# MCP4725_Breakout.net
KiCad netlist of a schematic drawn in EAGLE
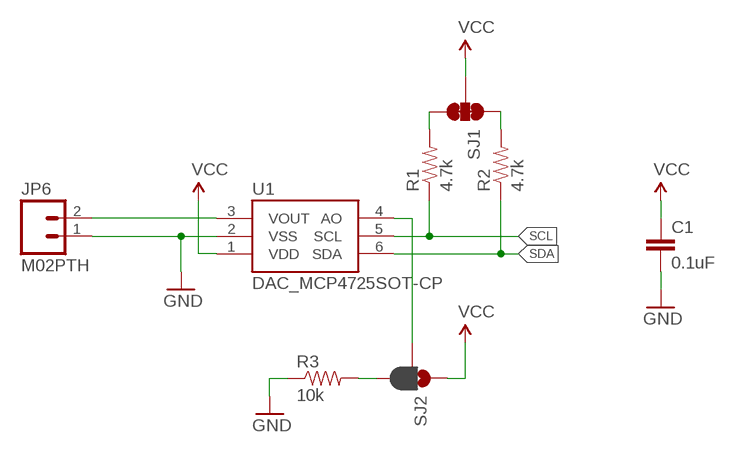
[diagram p0: schematic, sheet 1]

(export (version "E")
  (design (tool "Eeschema 10.0.6"))
  (components
    (comp (ref "C1")
      (value "0.1uF")
      (footprint "eagle-import:0603-CAP")
      (libsource (lib "eagle-import") (part "CAP0603-CAP"))
    )
    (comp (ref "JP6")
      (value "M02PTH")
      (footprint "eagle-import:1X02")
      (libsource (lib "eagle-import") (part "M02PTH"))
    )
    (comp (ref "R1")
      (value "4.7k")
      (footprint "eagle-import:0603-RES")
      (libsource (lib "eagle-import") (part "RESISTOR0603-RES"))
    )
    (comp (ref "R2")
      (value "4.7k")
      (footprint "eagle-import:0603-RES")
      (libsource (lib "eagle-import") (part "RESISTOR0603-RES"))
    )
    (comp (ref "R3")
      (value "10k")
      (footprint "eagle-import:0603-RES")
      (libsource (lib "eagle-import") (part "RESISTOR0603-RES"))
    )
    (comp (ref "SJ1")
      (value "JUMPER-PAD-3-NC_BY_TRACE")
      (footprint "eagle-import:PAD-JUMPER-3-3OF3_NC_BY_TRACE_YES_SILK_FULL_BOX")
      (libsource (lib "eagle-import") (part "JUMPER-PAD-3-NC_BY_TRACE"))
    )
    (comp (ref "SJ2")
      (value "JUMPER-PAD-3-2OF3_NC_BY_PASTE")
      (footprint "eagle-import:PAD-JUMPER-3-2OF3_NC_BY_PASTE_YES_SILK_FULL_BOX")
      (libsource (lib "eagle-import") (part "JUMPER-PAD-3-2OF3_NC_BY_PASTE"))
    )
    (comp (ref "U1")
      (value "DAC_MCP4725SOT-CP")
      (footprint "eagle-import:SOT23-6-MCP4725")
      (libsource (lib "eagle-import") (part "DAC_MCP4725SOT-CP"))
    )
  )
  (nets
    (net (code "1") (name "GND") (class "Default")
      (node (ref "C1") (pin "2") (pinfunction "2_2") (pintype "passive"))
      (node (ref "JP6") (pin "1") (pinfunction "1_1") (pintype "passive"))
      (node (ref "R3") (pin "1") (pinfunction "1_1") (pintype "passive"))
      (node (ref "U1") (pin "2") (pinfunction "VSS_2") (pintype "bidirectional"))
    )
    (net (code "2") (name "Net-(R1-Pad2)") (class "Default")
      (node (ref "R1") (pin "2") (pinfunction "2_2") (pintype "passive"))
      (node (ref "SJ1") (pin "3") (pinfunction "3_3") (pintype "passive"))
    )
    (net (code "3") (name "Net-(R2-Pad2)") (class "Default")
      (node (ref "R2") (pin "2") (pinfunction "2_2") (pintype "passive"))
      (node (ref "SJ1") (pin "1") (pinfunction "1_1") (pintype "passive"))
    )
    (net (code "4") (name "Net-(R3-Pad2)") (class "Default")
      (node (ref "R3") (pin "2") (pinfunction "2_2") (pintype "passive"))
      (node (ref "SJ2") (pin "3") (pinfunction "3_3") (pintype "passive"))
    )
    (net (code "5") (name "Net-(U1-AO)") (class "Default")
      (node (ref "SJ2") (pin "2") (pinfunction "2_2") (pintype "passive"))
      (node (ref "U1") (pin "4") (pinfunction "AO_4") (pintype "bidirectional"))
    )
    (net (code "6") (name "Net-(U1-VOUT)") (class "Default")
      (node (ref "JP6") (pin "2") (pinfunction "2_2") (pintype "passive"))
      (node (ref "U1") (pin "3") (pinfunction "VOUT_3") (pintype "bidirectional"))
    )
    (net (code "7") (name "SCL") (class "Default")
      (node (ref "R1") (pin "1") (pinfunction "1_1") (pintype "passive"))
      (node (ref "U1") (pin "5") (pinfunction "SCL_5") (pintype "bidirectional"))
    )
    (net (code "8") (name "SDA") (class "Default")
      (node (ref "R2") (pin "1") (pinfunction "1_1") (pintype "passive"))
      (node (ref "U1") (pin "6") (pinfunction "SDA_6") (pintype "bidirectional"))
    )
    (net (code "9") (name "VCC") (class "Default")
      (node (ref "C1") (pin "1") (pinfunction "1_1") (pintype "passive"))
      (node (ref "SJ1") (pin "2") (pinfunction "2_2") (pintype "passive"))
      (node (ref "SJ2") (pin "1") (pinfunction "1_1") (pintype "passive"))
      (node (ref "U1") (pin "1") (pinfunction "VDD_1") (pintype "bidirectional"))
    )
  )
)
